# Mechanical.net
KiCad netlist of a schematic drawn in Altium Designer
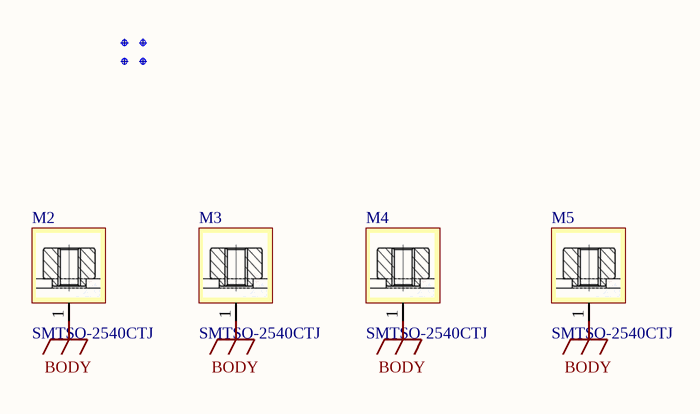
[diagram p0: Mechanical.SchDoc]

(export (version "E")
  (design (tool "Eeschema 10.0.6"))
  (components
    (comp (ref "Fid1")
      (value "Fiducial mark")
      (footprint "Fiducial")
      (description "Fiducial Mark")
      (fields (field (name "PART NUMBER") "Fid-Mark") (field (name "MANUFACTURER") "N.A."))
      (libsource (lib "ParsaLibrary") (part "Fid-Mark"))
    )
    (comp (ref "Fid2")
      (value "Fiducial mark")
      (footprint "Fiducial")
      (description "Fiducial Mark")
      (fields (field (name "PART NUMBER") "Fid-Mark") (field (name "MANUFACTURER") "N.A."))
      (libsource (lib "ParsaLibrary") (part "Fid-Mark"))
    )
    (comp (ref "Fid3")
      (value "Fiducial mark")
      (footprint "Fiducial")
      (description "Fiducial Mark")
      (fields (field (name "PART NUMBER") "Fid-Mark") (field (name "MANUFACTURER") "N.A."))
      (libsource (lib "ParsaLibrary") (part "Fid-Mark"))
    )
    (comp (ref "Fid4")
      (value "Fiducial mark")
      (footprint "Fiducial")
      (description "Fiducial Mark")
      (fields (field (name "PART NUMBER") "Fid-Mark") (field (name "MANUFACTURER") "N.A."))
      (libsource (lib "ParsaLibrary") (part "Fid-Mark"))
    )
    (comp (ref "M2")
      (value "SMTSO-2540CTJ")
      (footprint "SMTSO-2540CTJ")
      (libsource (lib "Schlib1") (part "SMTSO-2540CTJ"))
    )
    (comp (ref "M3")
      (value "SMTSO-2540CTJ")
      (footprint "SMTSO-2540CTJ")
      (libsource (lib "Schlib1") (part "SMTSO-2540CTJ"))
    )
    (comp (ref "M4")
      (value "SMTSO-2540CTJ")
      (footprint "SMTSO-2540CTJ")
      (libsource (lib "Schlib1") (part "SMTSO-2540CTJ"))
    )
    (comp (ref "M5")
      (value "SMTSO-2540CTJ")
      (footprint "SMTSO-2540CTJ")
      (libsource (lib "Schlib1") (part "SMTSO-2540CTJ"))
    )
  )
  (nets
    (net (code "1") (name "BODY") (class "Default")
      (node (ref "M2") (pin "1") (pinfunction "1_1") (pintype "passive"))
      (node (ref "M3") (pin "1") (pinfunction "1_1") (pintype "passive"))
      (node (ref "M4") (pin "1") (pinfunction "1_1") (pintype "passive"))
      (node (ref "M5") (pin "1") (pinfunction "1_1") (pintype "passive"))
    )
  )
)
